# Valve.net
KiCad netlist of a schematic drawn in Altium Designer
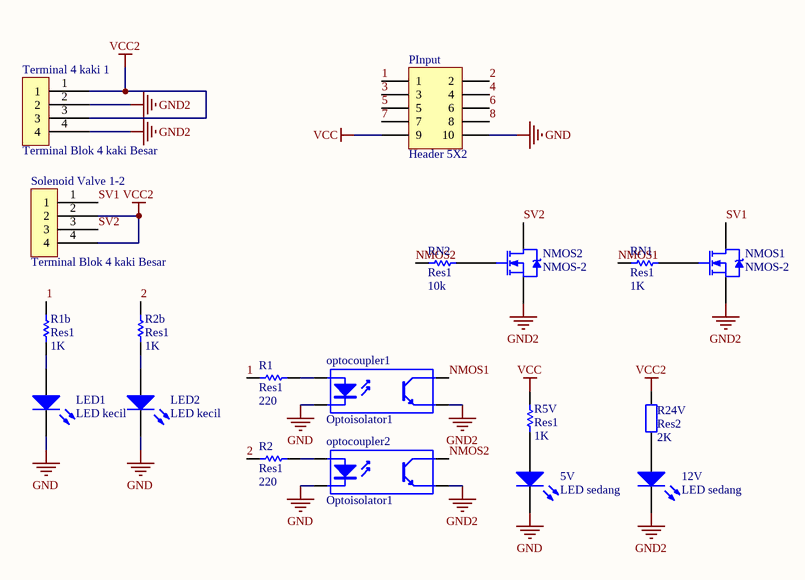
[diagram p0: Valve.SchDoc]

(export (version "E")
  (design (tool "Eeschema 10.0.6"))
  (components
    (comp (ref "5V")
      (value "LED sedang")
      (footprint "LED sedang")
      (libsource (lib "agfa other components") (part "LED sedang"))
    )
    (comp (ref "12V")
      (value "LED sedang")
      (footprint "LED sedang")
      (libsource (lib "agfa other components") (part "LED sedang"))
    )
    (comp (ref "LED1")
      (value "LED kecil")
      (footprint "LED kecil")
      (libsource (lib "agfa other components") (part "LED kecil"))
    )
    (comp (ref "LED2")
      (value "LED kecil")
      (footprint "LED kecil")
      (libsource (lib "agfa other components") (part "LED kecil"))
    )
    (comp (ref "NMOS1")
      (value "NMOS-2")
      (footprint "TO-220AB")
      (description "N-Channel Power MOSFET")
      (fields (field (name "PUBLISHER") "Altium Limited"))
      (libsource (lib "Miscellaneous Devices") (part "NMOS-2"))
    )
    (comp (ref "NMOS2")
      (value "NMOS-2")
      (footprint "TO-220AB")
      (description "N-Channel Power MOSFET")
      (fields (field (name "PUBLISHER") "Altium Limited"))
      (libsource (lib "Miscellaneous Devices") (part "NMOS-2"))
    )
    (comp (ref "optocoupler1")
      (value "Optoisolator1")
      (footprint "DIP-4")
      (description "4-Pin Phototransistor Optocoupler")
      (fields (field (name "PUBLISHER") "Altium Limited"))
      (libsource (lib "Miscellaneous Devices") (part "Optoisolator1"))
    )
    (comp (ref "optocoupler2")
      (value "Optoisolator1")
      (footprint "DIP-4")
      (description "4-Pin Phototransistor Optocoupler")
      (fields (field (name "PUBLISHER") "Altium Limited"))
      (libsource (lib "Miscellaneous Devices") (part "Optoisolator1"))
    )
    (comp (ref "PInput")
      (value "Header 5X2")
      (footprint "HDR2X5")
      (description "Header, 5-Pin, Dual row")
      (fields (field (name "PUBLISHER") "Altium Limited"))
      (libsource (lib "Miscellaneous Connectors") (part "Header 5X2"))
    )
    (comp (ref "R1")
      (value "Res1")
      (footprint "AXIAL-0.3")
      (description "Resistor")
      (fields (field (name "ALTIUM_VALUE") "220") (field (name "PUBLISHER") "Altium Limited"))
      (libsource (lib "Miscellaneous Devices") (part "Res1"))
    )
    (comp (ref "R1b")
      (value "Res1")
      (footprint "AXIAL-0.3")
      (description "Resistor")
      (fields (field (name "ALTIUM_VALUE") "1K") (field (name "PUBLISHER") "Altium Limited"))
      (libsource (lib "Miscellaneous Devices") (part "Res1"))
    )
    (comp (ref "R2")
      (value "Res1")
      (footprint "AXIAL-0.3")
      (description "Resistor")
      (fields (field (name "ALTIUM_VALUE") "220") (field (name "PUBLISHER") "Altium Limited"))
      (libsource (lib "Miscellaneous Devices") (part "Res1"))
    )
    (comp (ref "R2b")
      (value "Res1")
      (footprint "AXIAL-0.3")
      (description "Resistor")
      (fields (field (name "ALTIUM_VALUE") "1K") (field (name "PUBLISHER") "Altium Limited"))
      (libsource (lib "Miscellaneous Devices") (part "Res1"))
    )
    (comp (ref "R5V")
      (value "Res1")
      (footprint "AXIAL-0.3")
      (description "Resistor")
      (fields (field (name "ALTIUM_VALUE") "1K") (field (name "PUBLISHER") "Altium Limited"))
      (libsource (lib "Miscellaneous Devices") (part "Res1"))
    )
    (comp (ref "R24V")
      (value "Res2")
      (footprint "AXIAL-0.4")
      (description "Resistor")
      (fields (field (name "ALTIUM_VALUE") "2K") (field (name "PUBLISHER") "Altium Limited"))
      (libsource (lib "Miscellaneous Devices") (part "Res2"))
    )
    (comp (ref "RN1")
      (value "Res1")
      (footprint "AXIAL-0.3")
      (description "Resistor")
      (fields (field (name "ALTIUM_VALUE") "1K") (field (name "PUBLISHER") "Altium Limited"))
      (libsource (lib "Miscellaneous Devices") (part "Res1"))
    )
    (comp (ref "RN2")
      (value "Res1")
      (footprint "AXIAL-0.3")
      (description "Resistor")
      (fields (field (name "ALTIUM_VALUE") "10k") (field (name "PUBLISHER") "Altium Limited"))
      (libsource (lib "Miscellaneous Devices") (part "Res1"))
    )
    (comp (ref "Solenoid Valve 1-2")
      (value "Terminal Blok 4 kaki Besar")
      (footprint "TERMINAL 4 KAKI")
      (libsource (lib "Library Ausiher") (part "Terminal Blok 4 kaki"))
    )
    (comp (ref "Terminal 4 kaki 1")
      (value "Terminal Blok 4 kaki Besar")
      (footprint "TERMINAL 4 KAKI")
      (libsource (lib "Library Ausiher") (part "Terminal Blok 4 kaki"))
    )
  )
  (nets
    (net (code "1") (name "/1") (class "Default")
      (node (ref "PInput") (pin "1") (pinfunction "1_1") (pintype "passive"))
      (node (ref "R1") (pin "1") (pinfunction "1_1") (pintype "passive"))
      (node (ref "R1b") (pin "2") (pinfunction "2_2") (pintype "passive"))
    )
    (net (code "2") (name "/2") (class "Default")
      (node (ref "PInput") (pin "2") (pinfunction "2_2") (pintype "passive"))
      (node (ref "R2") (pin "1") (pinfunction "1_1") (pintype "passive"))
      (node (ref "R2b") (pin "2") (pinfunction "2_2") (pintype "passive"))
    )
    (net (code "3") (name "/3") (class "Default")
      (node (ref "PInput") (pin "3") (pinfunction "3_3") (pintype "passive"))
    )
    (net (code "4") (name "/4") (class "Default")
      (node (ref "PInput") (pin "4") (pinfunction "4_4") (pintype "passive"))
    )
    (net (code "5") (name "/5") (class "Default")
      (node (ref "PInput") (pin "5") (pinfunction "5_5") (pintype "passive"))
    )
    (net (code "6") (name "/6") (class "Default")
      (node (ref "PInput") (pin "6") (pinfunction "6_6") (pintype "passive"))
    )
    (net (code "7") (name "/7") (class "Default")
      (node (ref "PInput") (pin "7") (pinfunction "7_7") (pintype "passive"))
    )
    (net (code "8") (name "/8") (class "Default")
      (node (ref "PInput") (pin "8") (pinfunction "8_8") (pintype "passive"))
    )
    (net (code "9") (name "/NMOS1") (class "Default")
      (node (ref "RN1") (pin "1") (pinfunction "1_1") (pintype "passive"))
      (node (ref "optocoupler1") (pin "4") (pinfunction "C_4") (pintype "passive"))
    )
    (net (code "10") (name "/NMOS2") (class "Default")
      (node (ref "RN2") (pin "1") (pinfunction "1_1") (pintype "passive"))
      (node (ref "optocoupler2") (pin "4") (pinfunction "C_4") (pintype "passive"))
    )
    (net (code "11") (name "/SV1") (class "Default")
      (node (ref "NMOS1") (pin "2") (pinfunction "D_2") (pintype "passive"))
      (node (ref "Solenoid Valve 1-2") (pin "1") (pinfunction "1_1") (pintype "passive"))
    )
    (net (code "12") (name "/SV2") (class "Default")
      (node (ref "NMOS2") (pin "2") (pinfunction "D_2") (pintype "passive"))
      (node (ref "Solenoid Valve 1-2") (pin "3") (pinfunction "3_3") (pintype "passive"))
    )
    (net (code "13") (name "GND") (class "Default")
      (node (ref "5V") (pin "2") (pinfunction "K_2") (pintype "passive"))
      (node (ref "LED1") (pin "2") (pinfunction "K_2") (pintype "passive"))
      (node (ref "LED2") (pin "2") (pinfunction "K_2") (pintype "passive"))
      (node (ref "PInput") (pin "10") (pinfunction "10_10") (pintype "passive"))
      (node (ref "optocoupler1") (pin "2") (pinfunction "K_2") (pintype "passive"))
      (node (ref "optocoupler2") (pin "2") (pinfunction "K_2") (pintype "passive"))
    )
    (net (code "14") (name "GND2") (class "Default")
      (node (ref "12V") (pin "2") (pinfunction "K_2") (pintype "passive"))
      (node (ref "NMOS1") (pin "3") (pinfunction "S_3") (pintype "passive"))
      (node (ref "NMOS2") (pin "3") (pinfunction "S_3") (pintype "passive"))
      (node (ref "Terminal 4 kaki 1") (pin "2") (pinfunction "2_2") (pintype "passive"))
      (node (ref "Terminal 4 kaki 1") (pin "4") (pinfunction "4_4") (pintype "passive"))
      (node (ref "optocoupler1") (pin "3") (pinfunction "E_3") (pintype "passive"))
      (node (ref "optocoupler2") (pin "3") (pinfunction "E_3") (pintype "passive"))
    )
    (net (code "15") (name "Net-(5V-A)") (class "Default")
      (node (ref "5V") (pin "1") (pinfunction "A_1") (pintype "passive"))
      (node (ref "R5V") (pin "1") (pinfunction "1_1") (pintype "passive"))
    )
    (net (code "16") (name "Net-(12V-A)") (class "Default")
      (node (ref "12V") (pin "1") (pinfunction "A_1") (pintype "passive"))
      (node (ref "R24V") (pin "1") (pinfunction "1_1") (pintype "passive"))
    )
    (net (code "17") (name "Net-(LED1-A)") (class "Default")
      (node (ref "LED1") (pin "1") (pinfunction "A_1") (pintype "passive"))
      (node (ref "R1b") (pin "1") (pinfunction "1_1") (pintype "passive"))
    )
    (net (code "18") (name "Net-(LED2-A)") (class "Default")
      (node (ref "LED2") (pin "1") (pinfunction "A_1") (pintype "passive"))
      (node (ref "R2b") (pin "1") (pinfunction "1_1") (pintype "passive"))
    )
    (net (code "19") (name "Net-(NMOS1-G)") (class "Default")
      (node (ref "NMOS1") (pin "1") (pinfunction "G_1") (pintype "passive"))
      (node (ref "RN1") (pin "2") (pinfunction "2_2") (pintype "passive"))
    )
    (net (code "20") (name "Net-(NMOS2-G)") (class "Default")
      (node (ref "NMOS2") (pin "1") (pinfunction "G_1") (pintype "passive"))
      (node (ref "RN2") (pin "2") (pinfunction "2_2") (pintype "passive"))
    )
    (net (code "21") (name "Net-(optocoupler1-A)") (class "Default")
      (node (ref "R1") (pin "2") (pinfunction "2_2") (pintype "passive"))
      (node (ref "optocoupler1") (pin "1") (pinfunction "A_1") (pintype "passive"))
    )
    (net (code "22") (name "Net-(optocoupler2-A)") (class "Default")
      (node (ref "R2") (pin "2") (pinfunction "2_2") (pintype "passive"))
      (node (ref "optocoupler2") (pin "1") (pinfunction "A_1") (pintype "passive"))
    )
    (net (code "23") (name "VCC") (class "Default")
      (node (ref "PInput") (pin "9") (pinfunction "9_9") (pintype "passive"))
      (node (ref "R5V") (pin "2") (pinfunction "2_2") (pintype "passive"))
    )
    (net (code "24") (name "VCC2") (class "Default")
      (node (ref "R24V") (pin "2") (pinfunction "2_2") (pintype "passive"))
      (node (ref "Solenoid Valve 1-2") (pin "2") (pinfunction "2_2") (pintype "passive"))
      (node (ref "Solenoid Valve 1-2") (pin "4") (pinfunction "4_4") (pintype "passive"))
      (node (ref "Terminal 4 kaki 1") (pin "1") (pinfunction "1_1") (pintype "passive"))
      (node (ref "Terminal 4 kaki 1") (pin "3") (pinfunction "3_3") (pintype "passive"))
    )
  )
)
